# Flexi_Quark_board.net
KiCad netlist of a schematic drawn in Altium Designer
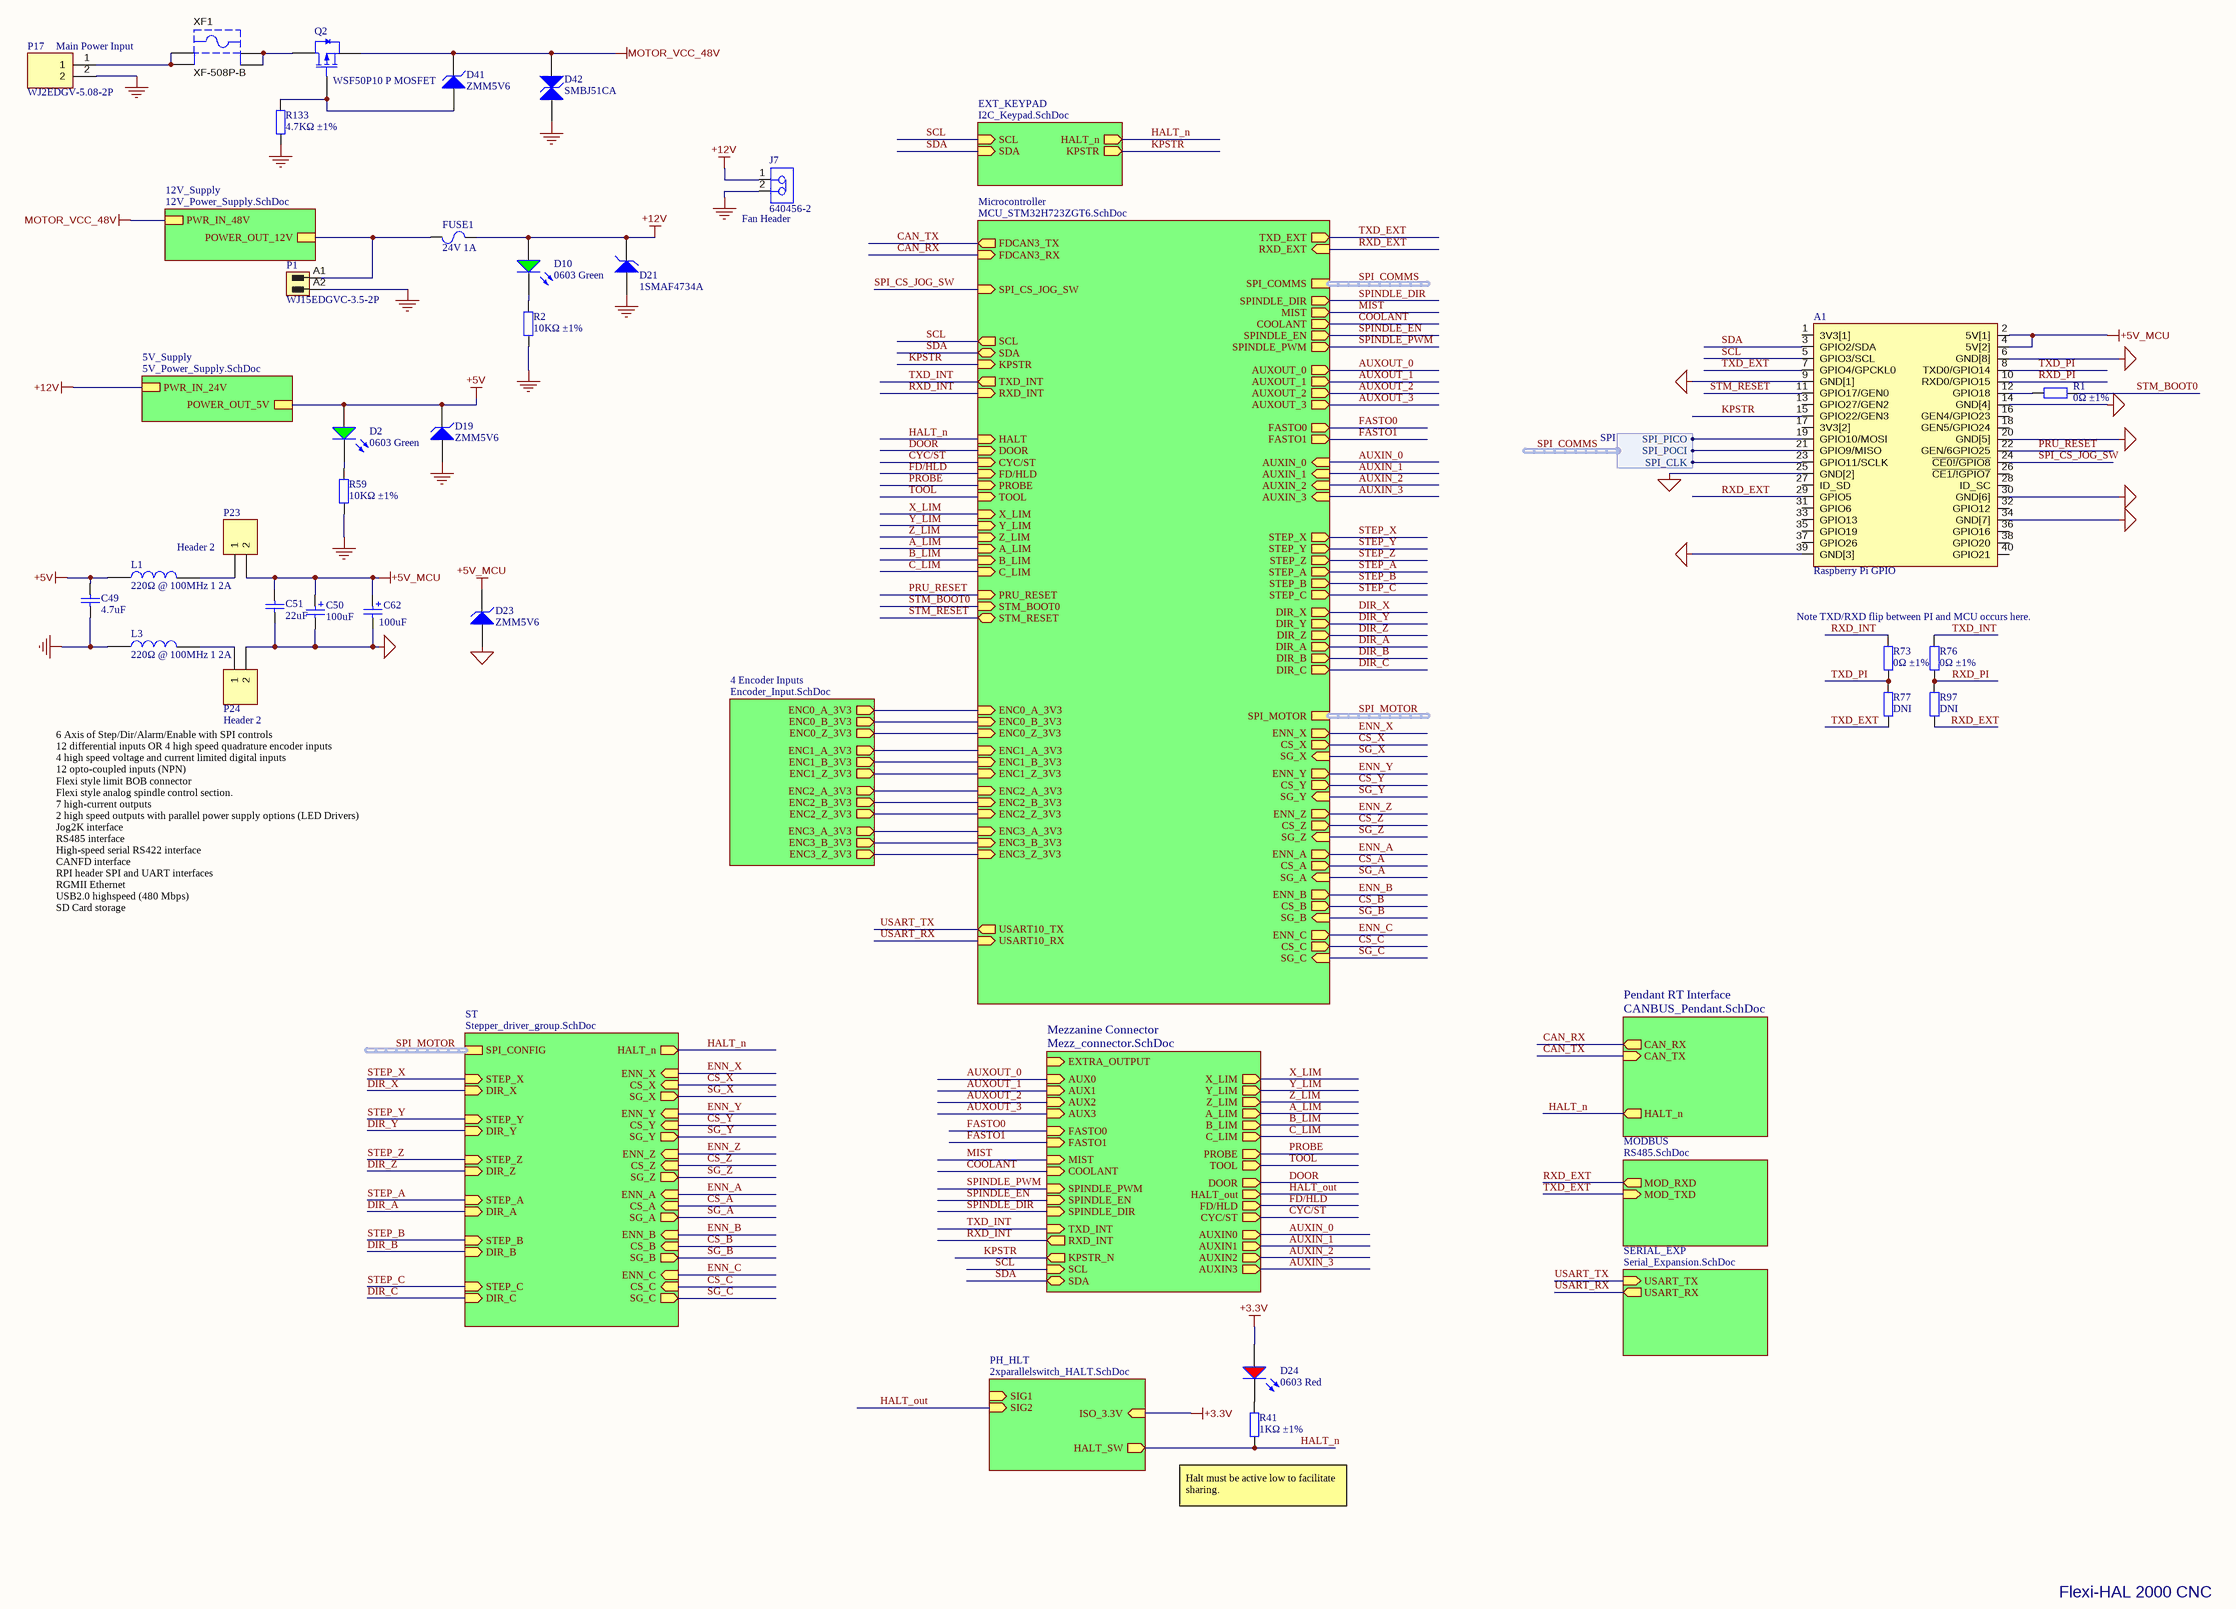
[diagram p0: Flexi_Quark_board.SchDoc]

(export (version "E")
  (design (tool "Eeschema 10.0.6"))
  (components
    (comp (ref "A1")
      (value "Raspberry Pi GPIO")
      (footprint "MODULE_RASPBERRY_PI_4_MODEL_B")
      (description "Raspberry Pi Zero WH _Zero W with Headers_")
      (fields (field (name "MP") "DS1023-2*20SF11") (field (name "MF") "CONNFLY Elec"))
      (libsource (lib "Universal_CNC_Breakout") (part "ADA3708"))
    )
    (comp (ref "C49")
      (value "4.7uF")
      (footprint "0603_C")
      (description "Chip capacitors")
      (fields
        (field (name "MANUFACTURER") "Samsung Electro-Mechanics")
        (field (name "PARTNUMBER") "CL10A475KO8NNNC")
      )
      (libsource (lib "Cap") (part "0603 4.7uF (475) 10% 16V"))
    )
    (comp (ref "C50")
      (value "100uF")
      (footprint "CASE-B_3528")
      (description "Tantalum capacitor")
      (fields (field (name "MANUFACTURER") "AVX") (field (name "PARTNUMBER") "TAJB107K006RNJ"))
      (libsource (lib "Cap") (part "3528 100uF (107) 10% 6.3V"))
    )
    (comp (ref "C51")
      (value "22uF")
      (footprint "0805_C")
      (description "Chip capacitors")
      (fields
        (field (name "MANUFACTURER") "Samsung Electro-Mechanics")
        (field (name "PARTNUMBER") "CL21A226MAQNNNE")
      )
      (libsource (lib "Cap") (part "0805 22uF (226) 20% 25V"))
    )
    (comp (ref "C62")
      (value "100uF")
      (footprint "WCAP-ASLI_D6.3H7.7")
      (fields (field (name "MANUFACTURER") "Capxon International Elec"))
      (libsource (lib "IQAnalog") (part "865080445010"))
    )
    (comp (ref "D2")
      (value "0603 Green")
      (footprint "0603_LED_S1")
      (description "LED")
      (libsource (lib "LED") (part "0603 LED Green"))
    )
    (comp (ref "D10")
      (value "0603 Green")
      (footprint "0603_LED_S1")
      (description "LED")
      (libsource (lib "LED") (part "0603 LED Green"))
    )
    (comp (ref "D19")
      (value "ZMM5V6")
      (footprint "LL-34")
      (description "500mW - 0.1uA @ 1V 5.6V LL-34 Zener Diodes ROHS")
      (libsource (lib "Zener") (part "LL-34 ZMM5V6"))
    )
    (comp (ref "D21")
      (value "1SMAF4734A")
      (footprint "DIOM5226X240N")
      (description "27V ±5% 1W 500nA @ 20.5V SMA(DO-214AC) Zener Diodes RoHS")
      (libsource (lib "PrintNC_GRBLHAL_Breakout") (part "BZT52C27"))
    )
    (comp (ref "D23")
      (value "ZMM5V6")
      (footprint "LL-34")
      (description "500mW - 0.1uA @ 1V 5.6V LL-34 Zener Diodes ROHS")
      (libsource (lib "Zener") (part "LL-34 ZMM5V6"))
    )
    (comp (ref "D24")
      (value "0603 Red")
      (footprint "0603_LED_S1")
      (description "LED")
      (libsource (lib "LED") (part "0603 LED Red"))
    )
    (comp (ref "D41")
      (value "ZMM5V6")
      (footprint "LL-34")
      (description "500mW - 0.1uA @ 1V 5.6V LL-34 Zener Diodes ROHS")
      (libsource (lib "Zener") (part "LL-34 ZMM5V6"))
    )
    (comp (ref "D42")
      (value "SMBJ51CA")
      (footprint "SMB(DO-214AA)_S1")
      (description "82.4V 56.7V 51V SMB(DO-214AA) TVS ROHS")
      (libsource (lib "Diode") (part "SMB/DO-214AA P6SMB6.8CA"))
    )
    (comp (ref "FUSE1")
      (value "24V 1A")
      (footprint "1206_C")
      (description "24V 1A 0.1s 1206 PTC Resettable Fuses RoHS")
      (fields
        (field (name "MANUFACTURER") "Jinrui Electronic Materials Co.")
        (field (name "PARTNUMBER") "JK-nSMD050-24")
      )
      (libsource (lib "PrintNC_GRBLHAL_Breakout") (part "JK-nSMD050-24"))
    )
    (comp (ref "J7")
      (value "640456-2")
      (footprint "TECO-640456-2_V")
      (fields (field (name "MANUFACTURER") "TE Connectivity"))
      (libsource (lib "Altium Content Vault") (part "CN-2P-F-QF2"))
    )
    (comp (ref "L1")
      (value "220Ω @ 100MHz 1 2A")
      (footprint "0805_C")
      (description "220Ω @ 100MHz 1 2A 150mΩ 0805 Ferrite Beads ROHS")
      (libsource (lib "FBEAD") (part "0402 220R@100Mhz 0.1A"))
    )
    (comp (ref "L3")
      (value "220Ω @ 100MHz 1 2A")
      (footprint "0805_C")
      (description "220Ω @ 100MHz 1 2A 150mΩ 0805 Ferrite Beads ROHS")
      (libsource (lib "FBEAD") (part "0402 220R@100Mhz 0.1A"))
    )
    (comp (ref "P1")
      (value "WJ15EDGVC-3.5-2P")
      (footprint "691321100002")
      (fields (field (name "MANUFACTURER") "Weidmueller"))
      (libsource (lib "Universal_CNC_Breakout") (part "3.5mm Terminal Header 2p"))
    )
    (comp (ref "P17")
      (value "WJ2EDGV-5.08-2P")
      (footprint "WJ2EDGV5082P")
      (description "5.08mm Green Board Edge/Receptacle-Open Straight,P=5.08mm Pluggable System Terminal Block ROHS")
      (fields (field (name "MANUFACTURER") "Kangnex"))
      (libsource (lib "Sienci_Labs") (part "WJ2EDGV-5.08-2P"))
    )
    (comp (ref "P23")
      (value "Header 2")
      (footprint "HDR1X2")
      (description "Header, 2-Pin")
      (fields (field (name "PUBLISHER") "Altium Limited"))
      (libsource (lib "Miscellaneous Connectors") (part "Header 2"))
    )
    (comp (ref "P24")
      (value "Header 2")
      (footprint "HDR1X2")
      (description "Header, 2-Pin")
      (fields (field (name "PUBLISHER") "Altium Limited"))
      (libsource (lib "") (part "Header 2_1"))
    )
    (comp (ref "Q2")
      (value "WSF50P10 P MOSFET")
      (footprint "TO-252-2-180")
      (description "100V 34A 32mΩ@10V,18A 96W P Channel TO-252-2 MOSFETs ROHS")
      (libsource (lib "MOS") (part "WSF50P10 P TO-252-2"))
    )
    (comp (ref "R1")
      (value "0Ω ±1%")
      (footprint "0603_R")
      (description "Chip resistor")
      (fields (field (name "MANUFACTURER") "Uniroyal Elec") (field (name "PARTNUMBER") "0603WAF0000T5E"))
      (libsource (lib "RES") (part "0603 0R (0R0) 1%"))
    )
    (comp (ref "R2")
      (value "10KΩ ±1%")
      (footprint "0603_R")
      (description "Chip resistor")
      (fields (field (name "MANUFACTURER") "Uniroyal Elec") (field (name "PARTNUMBER") "0603WAF1002T5E"))
      (libsource (lib "RES") (part "0603 10K (1002) 1%"))
    )
    (comp (ref "R41")
      (value "1KΩ ±1%")
      (footprint "0603_R")
      (description "Chip resistor")
      (fields (field (name "MANUFACTURER") "Uniroyal Elec") (field (name "PARTNUMBER") "0603WAF1001T5E"))
      (libsource (lib "RES") (part "0603 1K (1001) 1%"))
    )
    (comp (ref "R59")
      (value "10KΩ ±1%")
      (footprint "0603_R")
      (description "Chip resistor")
      (fields (field (name "MANUFACTURER") "Uniroyal Elec") (field (name "PARTNUMBER") "0603WAF1002T5E"))
      (libsource (lib "RES") (part "0603 10K (1002) 1%"))
    )
    (comp (ref "R73")
      (value "0Ω ±1%")
      (footprint "0402_R")
      (description "Chip resistor")
      (fields (field (name "POWER") "1/16W") (field (name "MANUFACTURER") "Uniroyal Elec"))
      (libsource (lib "RES") (part "0402 0R (0R0) 1%"))
    )
    (comp (ref "R76")
      (value "0Ω ±1%")
      (footprint "0402_R")
      (description "Chip resistor")
      (fields (field (name "POWER") "1/16W") (field (name "MANUFACTURER") "Uniroyal Elec"))
      (libsource (lib "RES") (part "0402 0R (0R0) 1%"))
    )
    (comp (ref "R77")
      (value "DNI")
      (footprint "0402_R")
      (description "Chip resistor")
      (fields (field (name "POWER") "1/16W") (field (name "MANUFACTURER") "Uniroyal Elec"))
      (libsource (lib "RES") (part "0402 0R (0R0) 1%"))
    )
    (comp (ref "R97")
      (value "DNI")
      (footprint "0402_R")
      (description "Chip resistor")
      (fields (field (name "POWER") "1/16W") (field (name "MANUFACTURER") "Uniroyal Elec"))
      (libsource (lib "RES") (part "0402 0R (0R0) 1%"))
    )
    (comp (ref "R133")
      (value "4.7KΩ ±1%")
      (footprint "0603_R")
      (description "Chip resistor")
      (fields (field (name "MANUFACTURER") "Uniroyal Elec") (field (name "PARTNUMBER") "0603WAF4701T5E"))
      (libsource (lib "RES") (part "0603 4.7K (4701) 1%"))
    )
    (comp (ref "XF1")
      (value "XF-508P-B")
      (footprint "KSTN-3568_V")
      (description "Fuse Holder, 20 A, 500 V, -50 to 145 degC, 4-Pin THD, RoHS")
      (fields (field (name "MANUFACTURER") "XFCN"))
      (libsource (lib "Sienci_Labs") (part "XF-508P-B"))
    )
  )
  (nets
    (net (code "4") (name "+3.3V") (class "Default")
      (node (ref "D24") (pin "A") (pinfunction "A_A") (pintype "passive"))
    )
    (net (code "5") (name "+5V") (class "Default")
      (node (ref "C49") (pin "2") (pinfunction "2_2") (pintype "passive"))
      (node (ref "D19") (pin "2") (pinfunction "K_2") (pintype "passive"))
      (node (ref "D2") (pin "A") (pinfunction "A_A") (pintype "passive"))
      (node (ref "L1") (pin "1") (pinfunction "1_1") (pintype "passive"))
    )
    (net (code "6") (name "+5V_MCU") (class "Default")
      (node (ref "A1") (pin "2") (pinfunction "5V[1]_2") (pintype "power_in"))
      (node (ref "A1") (pin "4") (pinfunction "5V[2]_4") (pintype "power_in"))
      (node (ref "C50") (pin "1") (pinfunction "1_1") (pintype "passive"))
      (node (ref "C51") (pin "2") (pinfunction "2_2") (pintype "passive"))
      (node (ref "C62") (pin "1") (pinfunction "P_1") (pintype "passive"))
      (node (ref "D23") (pin "2") (pinfunction "K_2") (pintype "passive"))
      (node (ref "P23") (pin "2") (pinfunction "2_2") (pintype "passive"))
    )
    (net (code "7") (name "+12V") (class "Default")
      (node (ref "D10") (pin "A") (pinfunction "A_A") (pintype "passive"))
      (node (ref "D21") (pin "2") (pinfunction "K_2") (pintype "passive"))
      (node (ref "FUSE1") (pin "2") (pinfunction "2_2") (pintype "passive"))
      (node (ref "J7") (pin "1") (pinfunction "1_1") (pintype "passive"))
    )
    (net (code "58") (name "/HALT_n") (class "Default")
      (node (ref "R41") (pin "2") (pinfunction "2_2") (pintype "passive"))
    )
    (net (code "60") (name "/KPSTR") (class "Default")
      (node (ref "A1") (pin "15") (pinfunction "GPIO22/GEN3_15") (pintype "bidirectional"))
    )
    (net (code "62") (name "/POWER_OUT_12V") (class "Default")
      (node (ref "FUSE1") (pin "1") (pinfunction "1_1") (pintype "passive"))
      (node (ref "P1") (pin "A1") (pinfunction "A1_A1") (pintype "passive"))
    )
    (net (code "64") (name "/PRU_RESET") (class "Default")
      (node (ref "A1") (pin "22") (pinfunction "GEN/6GPIO25_22") (pintype "bidirectional"))
    )
    (net (code "65") (name "/RXD_EXT") (class "Default")
      (node (ref "A1") (pin "29") (pinfunction "GPIO5_29") (pintype "bidirectional"))
      (node (ref "R97") (pin "1") (pinfunction "1_1") (pintype "passive"))
    )
    (net (code "66") (name "/RXD_INT") (class "Default")
      (node (ref "R73") (pin "2") (pinfunction "2_2") (pintype "passive"))
    )
    (net (code "67") (name "/RXD_PI") (class "Default")
      (node (ref "A1") (pin "10") (pinfunction "RXD0/GPIO15_10") (pintype "bidirectional"))
      (node (ref "R76") (pin "1") (pinfunction "1_1") (pintype "passive"))
      (node (ref "R97") (pin "2") (pinfunction "2_2") (pintype "passive"))
    )
    (net (code "68") (name "/SCL") (class "Default")
      (node (ref "A1") (pin "5") (pinfunction "GPIO3/SCL_5") (pintype "bidirectional"))
    )
    (net (code "69") (name "/SDA") (class "Default")
      (node (ref "A1") (pin "3") (pinfunction "GPIO2/SDA_3") (pintype "bidirectional"))
    )
    (net (code "80") (name "/SPI_CLK") (class "Default")
      (node (ref "A1") (pin "23") (pinfunction "GPIO11/SCLK_23") (pintype "bidirectional"))
    )
    (net (code "82") (name "/SPI_CS_JOG_SW") (class "Default")
      (node (ref "A1") (pin "24") (pinfunction "~{CE0!/GPIO8}_24") (pintype "bidirectional"))
    )
    (net (code "83") (name "/SPI_PICO") (class "Default")
      (node (ref "A1") (pin "19") (pinfunction "GPIO10/MOSI_19") (pintype "bidirectional"))
    )
    (net (code "84") (name "/SPI_POCI") (class "Default")
      (node (ref "A1") (pin "21") (pinfunction "GPIO9/MISO_21") (pintype "bidirectional"))
    )
    (net (code "91") (name "/STM_BOOT0") (class "Default")
      (node (ref "R1") (pin "1") (pinfunction "1_1") (pintype "passive"))
    )
    (net (code "92") (name "/STM_RESET") (class "Default")
      (node (ref "A1") (pin "11") (pinfunction "GPIO17/GEN0_11") (pintype "bidirectional"))
    )
    (net (code "94") (name "/TXD_EXT") (class "Default")
      (node (ref "A1") (pin "7") (pinfunction "GPIO4/GPCKL0_7") (pintype "bidirectional"))
      (node (ref "R77") (pin "1") (pinfunction "1_1") (pintype "passive"))
    )
    (net (code "95") (name "/TXD_INT") (class "Default")
      (node (ref "R76") (pin "2") (pinfunction "2_2") (pintype "passive"))
    )
    (net (code "96") (name "/TXD_PI") (class "Default")
      (node (ref "A1") (pin "8") (pinfunction "TXD0/GPIO14_8") (pintype "bidirectional"))
      (node (ref "R73") (pin "1") (pinfunction "1_1") (pintype "passive"))
      (node (ref "R77") (pin "2") (pinfunction "2_2") (pintype "passive"))
    )
    (net (code "104") (name "GND") (class "Default")
      (node (ref "C49") (pin "1") (pinfunction "1_1") (pintype "passive"))
      (node (ref "D19") (pin "1") (pinfunction "A_1") (pintype "passive"))
      (node (ref "D21") (pin "1") (pinfunction "A_1") (pintype "passive"))
      (node (ref "D42") (pin "1") (pinfunction "A_1") (pintype "passive"))
      (node (ref "J7") (pin "2") (pinfunction "2_2") (pintype "passive"))
      (node (ref "L3") (pin "1") (pinfunction "1_1") (pintype "passive"))
      (node (ref "P1") (pin "A2") (pinfunction "A2_A2") (pintype "passive"))
      (node (ref "P17") (pin "2") (pinfunction "2_2") (pintype "passive"))
      (node (ref "R133") (pin "1") (pinfunction "1_1") (pintype "passive"))
      (node (ref "R2") (pin "1") (pinfunction "1_1") (pintype "passive"))
      (node (ref "R59") (pin "1") (pinfunction "1_1") (pintype "passive"))
    )
    (net (code "105") (name "MCU_GND") (class "Default")
      (node (ref "A1") (pin "14") (pinfunction "GND[4]_14") (pintype "power_in"))
      (node (ref "A1") (pin "20") (pinfunction "GND[5]_20") (pintype "power_in"))
      (node (ref "A1") (pin "25") (pinfunction "GND[2]_25") (pintype "power_in"))
      (node (ref "A1") (pin "30") (pinfunction "GND[6]_30") (pintype "power_in"))
      (node (ref "A1") (pin "34") (pinfunction "GND[7]_34") (pintype "power_in"))
      (node (ref "A1") (pin "39") (pinfunction "GND[3]_39") (pintype "power_in"))
      (node (ref "A1") (pin "6") (pinfunction "GND[8]_6") (pintype "power_in"))
      (node (ref "A1") (pin "9") (pinfunction "GND[1]_9") (pintype "power_in"))
      (node (ref "C50") (pin "2") (pinfunction "2_2") (pintype "passive"))
      (node (ref "C51") (pin "1") (pinfunction "1_1") (pintype "passive"))
      (node (ref "C62") (pin "2") (pinfunction "N_2") (pintype "passive"))
      (node (ref "D23") (pin "1") (pinfunction "A_1") (pintype "passive"))
      (node (ref "P24") (pin "2") (pinfunction "2_2") (pintype "passive"))
    )
    (net (code "106") (name "MOTOR_VCC_48V") (class "Default")
      (node (ref "D41") (pin "2") (pinfunction "K_2") (pintype "passive"))
      (node (ref "D42") (pin "2") (pinfunction "K_2") (pintype "passive"))
      (node (ref "Q2") (pin "2") (pinfunction "S_2") (pintype "passive"))
    )
    (net (code "107") (name "Net-(A1-GPIO18)") (class "Default")
      (node (ref "A1") (pin "12") (pinfunction "GPIO18_12") (pintype "bidirectional"))
      (node (ref "R1") (pin "2") (pinfunction "2_2") (pintype "passive"))
    )
    (net (code "108") (name "Net-(D2-PadK)") (class "Default")
      (node (ref "D2") (pin "K") (pinfunction "K_K") (pintype "passive"))
      (node (ref "R59") (pin "2") (pinfunction "2_2") (pintype "passive"))
    )
    (net (code "109") (name "Net-(D10-PadK)") (class "Default")
      (node (ref "D10") (pin "K") (pinfunction "K_K") (pintype "passive"))
      (node (ref "R2") (pin "2") (pinfunction "2_2") (pintype "passive"))
    )
    (net (code "110") (name "Net-(D24-PadK)") (class "Default")
      (node (ref "D24") (pin "K") (pinfunction "K_K") (pintype "passive"))
      (node (ref "R41") (pin "1") (pinfunction "1_1") (pintype "passive"))
    )
    (net (code "111") (name "Net-(D41-A)") (class "Default")
      (node (ref "D41") (pin "1") (pinfunction "A_1") (pintype "passive"))
      (node (ref "Q2") (pin "1") (pinfunction "G_1") (pintype "passive"))
      (node (ref "R133") (pin "2") (pinfunction "2_2") (pintype "passive"))
    )
    (net (code "112") (name "Net-(L1-Pad2)") (class "Default")
      (node (ref "L1") (pin "2") (pinfunction "2_2") (pintype "passive"))
      (node (ref "P23") (pin "1") (pinfunction "1_1") (pintype "passive"))
    )
    (net (code "113") (name "Net-(L3-Pad2)") (class "Default")
      (node (ref "L3") (pin "2") (pinfunction "2_2") (pintype "passive"))
      (node (ref "P24") (pin "1") (pinfunction "1_1") (pintype "passive"))
    )
    (net (code "114") (name "Net-(P17-Pad1)") (class "Default")
      (node (ref "P17") (pin "1") (pinfunction "1_1") (pintype "passive"))
      (node (ref "XF1") (pin "1") (pinfunction "1_1") (pintype "passive"))
      (node (ref "XF1") (pin "2") (pinfunction "2_2") (pintype "passive"))
    )
    (net (code "115") (name "Net-(Q2-D)") (class "Default")
      (node (ref "Q2") (pin "3") (pinfunction "D_3") (pintype "passive"))
      (node (ref "XF1") (pin "3") (pinfunction "3_3") (pintype "passive"))
      (node (ref "XF1") (pin "4") (pinfunction "4_4") (pintype "passive"))
    )
    (net (code "116") (name "unconnected-(A1-3V3[1]-Pad1)") (class "Default")
      (node (ref "A1") (pin "1") (pinfunction "3V3[1]_1") (pintype "power_in"))
    )
    (net (code "117") (name "unconnected-(A1-3V3[2]-Pad17)") (class "Default")
      (node (ref "A1") (pin "17") (pinfunction "3V3[2]_17") (pintype "power_in"))
    )
    (net (code "118") (name "unconnected-(A1-GEN4{slash}GPIO23-Pad16)") (class "Default")
      (node (ref "A1") (pin "16") (pinfunction "GEN4/GPIO23_16") (pintype "bidirectional"))
    )
    (net (code "119") (name "unconnected-(A1-GEN5{slash}GPIO24-Pad18)") (class "Default")
      (node (ref "A1") (pin "18") (pinfunction "GEN5/GPIO24_18") (pintype "bidirectional"))
    )
    (net (code "120") (name "unconnected-(A1-GPIO6-Pad31)") (class "Default")
      (node (ref "A1") (pin "31") (pinfunction "GPIO6_31") (pintype "bidirectional"))
    )
    (net (code "121") (name "unconnected-(A1-GPIO12-Pad32)") (class "Default")
      (node (ref "A1") (pin "32") (pinfunction "GPIO12_32") (pintype "bidirectional"))
    )
    (net (code "122") (name "unconnected-(A1-GPIO13-Pad33)") (class "Default")
      (node (ref "A1") (pin "33") (pinfunction "GPIO13_33") (pintype "bidirectional"))
    )
    (net (code "123") (name "unconnected-(A1-GPIO16-Pad36)") (class "Default")
      (node (ref "A1") (pin "36") (pinfunction "GPIO16_36") (pintype "bidirectional"))
    )
    (net (code "124") (name "unconnected-(A1-GPIO19-Pad35)") (class "Default")
      (node (ref "A1") (pin "35") (pinfunction "GPIO19_35") (pintype "bidirectional"))
    )
    (net (code "125") (name "unconnected-(A1-GPIO20-Pad38)") (class "Default")
      (node (ref "A1") (pin "38") (pinfunction "GPIO20_38") (pintype "bidirectional"))
    )
    (net (code "126") (name "unconnected-(A1-GPIO21-Pad40)") (class "Default")
      (node (ref "A1") (pin "40") (pinfunction "GPIO21_40") (pintype "bidirectional"))
    )
    (net (code "127") (name "unconnected-(A1-GPIO26-Pad37)") (class "Default")
      (node (ref "A1") (pin "37") (pinfunction "GPIO26_37") (pintype "bidirectional"))
    )
    (net (code "128") (name "unconnected-(A1-GPIO27{slash}GEN2-Pad13)") (class "Default")
      (node (ref "A1") (pin "13") (pinfunction "GPIO27/GEN2_13") (pintype "bidirectional"))
    )
    (net (code "129") (name "unconnected-(A1-ID_SC-Pad28)") (class "Default")
      (node (ref "A1") (pin "28") (pinfunction "ID_SC_28") (pintype "bidirectional"))
    )
    (net (code "130") (name "unconnected-(A1-ID_SD-Pad27)") (class "Default")
      (node (ref "A1") (pin "27") (pinfunction "ID_SD_27") (pintype "bidirectional"))
    )
    (net (code "131") (name "unconnected-(A1-~{CE1{slash}!GPIO7}-Pad26)") (class "Default")
      (node (ref "A1") (pin "26") (pinfunction "~{CE1/!GPIO7}_26") (pintype "bidirectional"))
    )
  )
)
